# Filamint_Schematic.net
KiCad netlist of a schematic drawn in EAGLE
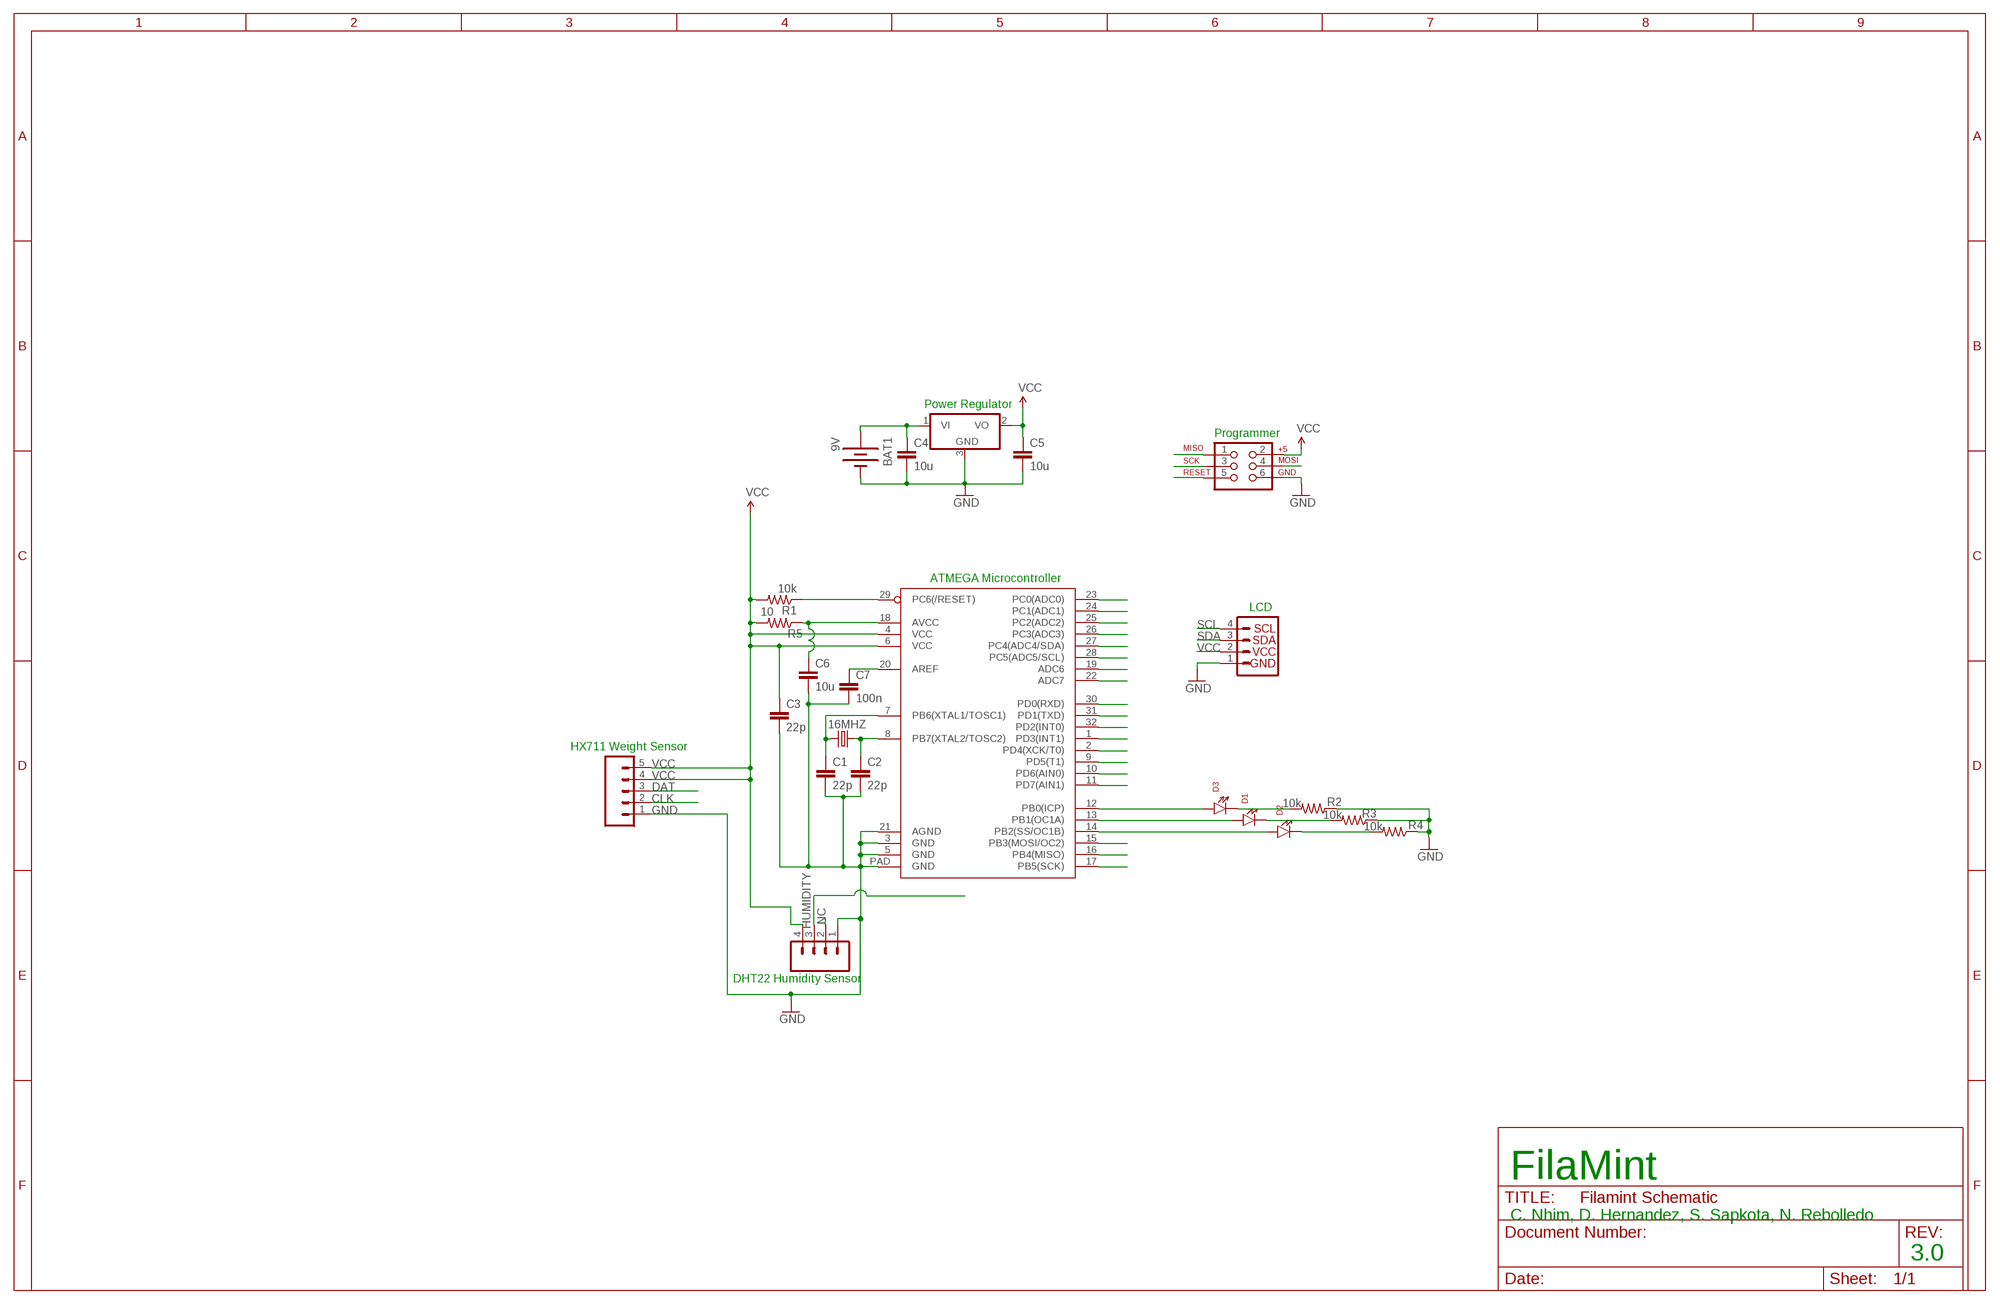
[diagram p0: schematic, sheet 1]

(export (version "E")
  (design (tool "Eeschema 10.0.6"))
  (components
    (comp (ref "16MHZ")
      (value "CSM-7X-DU")
      (footprint "eagle-import:CSM-7X-DU")
      (libsource (lib "eagle-import") (part "CSM-7X-DU"))
    )
    (comp (ref "BAT1")
      (value "9V")
      (footprint "eagle-import:BATTCON_9V")
      (libsource (lib "eagle-import") (part "BATTERY9V"))
    )
    (comp (ref "C1")
      (value "22p")
      (footprint "eagle-import:C025-024X044")
      (libsource (lib "eagle-import") (part "C-EU025-024X044"))
    )
    (comp (ref "C2")
      (value "22p")
      (footprint "eagle-import:C025-024X044")
      (libsource (lib "eagle-import") (part "C-EU025-024X044"))
    )
    (comp (ref "C3")
      (value "22p")
      (footprint "eagle-import:C025-024X044")
      (libsource (lib "eagle-import") (part "C-EU025-024X044"))
    )
    (comp (ref "C4")
      (value "10u")
      (footprint "eagle-import:C025-024X044")
      (libsource (lib "eagle-import") (part "C-EU025-024X044"))
    )
    (comp (ref "C5")
      (value "10u")
      (footprint "eagle-import:C025-024X044")
      (libsource (lib "eagle-import") (part "C-EU025-024X044"))
    )
    (comp (ref "C6")
      (value "10u")
      (footprint "eagle-import:C025-024X044")
      (libsource (lib "eagle-import") (part "C-EU025-024X044"))
    )
    (comp (ref "C7")
      (value "100n")
      (footprint "eagle-import:C025-024X044")
      (libsource (lib "eagle-import") (part "C-EU025-024X044"))
    )
    (comp (ref "D1")
      (value "LTE-302")
      (footprint "eagle-import:LTE-302")
      (libsource (lib "eagle-import") (part "LTE-302"))
    )
    (comp (ref "D2")
      (value "LTE-302")
      (footprint "eagle-import:LTE-302")
      (libsource (lib "eagle-import") (part "LTE-302"))
    )
    (comp (ref "D3")
      (value "LTE-302")
      (footprint "eagle-import:LTE-302")
      (libsource (lib "eagle-import") (part "LTE-302"))
    )
    (comp (ref "DHT22")
      (value "M04SMD2")
      (footprint "eagle-import:1X04-1MM-RA")
      (libsource (lib "eagle-import") (part "M04SMD2"))
    )
    (comp (ref "HX711")
      (value "M05SMD")
      (footprint "eagle-import:1X05-1MM")
      (libsource (lib "eagle-import") (part "M05SMD"))
    )
    (comp (ref "IC1")
      (value "7805DT")
      (footprint "eagle-import:TO252")
      (libsource (lib "eagle-import") (part "78DT05"))
    )
    (comp (ref "LCD")
      (value "I2C_STANDARD")
      (footprint "eagle-import:1X04")
      (libsource (lib "eagle-import") (part "I2C_STANDARD"))
    )
    (comp (ref "MICROCONTROLLER")
      (value "ATMEGA328P_MLFMLF32")
      (footprint "eagle-import:MLF32-PAD")
      (libsource (lib "eagle-import") (part "ATMEGA328P_MLFMLF32"))
    )
    (comp (ref "PROGRAMMER")
      (value "AVR_SPI_PRG_6PTH")
      (footprint "eagle-import:2X3")
      (libsource (lib "eagle-import") (part "AVR_SPI_PRG_6PTH"))
    )
    (comp (ref "R1")
      (value "10k")
      (footprint "eagle-import:0204_5")
      (libsource (lib "eagle-import") (part "R-US_0204/5"))
    )
    (comp (ref "R2")
      (value "10k")
      (footprint "eagle-import:0204_5")
      (libsource (lib "eagle-import") (part "R-US_0204/5"))
    )
    (comp (ref "R3")
      (value "10k")
      (footprint "eagle-import:0204_5")
      (libsource (lib "eagle-import") (part "R-US_0204/5"))
    )
    (comp (ref "R4")
      (value "10k")
      (footprint "eagle-import:0204_5")
      (libsource (lib "eagle-import") (part "R-US_0204/5"))
    )
    (comp (ref "R5")
      (value "10")
      (footprint "eagle-import:0204_5")
      (libsource (lib "eagle-import") (part "R-US_0204/5"))
    )
  )
  (nets
    (net (code "1") (name "/CLK") (class "Default")
      (node (ref "HX711") (pin "2") (pinfunction "2_2") (pintype "passive"))
    )
    (net (code "2") (name "/DAT") (class "Default")
      (node (ref "HX711") (pin "3") (pinfunction "3_3") (pintype "passive"))
    )
    (net (code "3") (name "/HUMIDITY") (class "Default")
      (node (ref "DHT22") (pin "3") (pinfunction "3_3") (pintype "passive"))
    )
    (net (code "4") (name "/MISO") (class "Default")
      (node (ref "MICROCONTROLLER") (pin "16") (pinfunction "PB4(MISO)_16") (pintype "bidirectional"))
      (node (ref "PROGRAMMER") (pin "1") (pinfunction "1_1") (pintype "passive"))
    )
    (net (code "5") (name "/MOSI") (class "Default")
      (node (ref "MICROCONTROLLER") (pin "15") (pinfunction "PB3(MOSI/OC2)_15") (pintype "bidirectional"))
      (node (ref "PROGRAMMER") (pin "4") (pinfunction "4_4") (pintype "passive"))
    )
    (net (code "6") (name "/NC") (class "Default")
      (node (ref "DHT22") (pin "2") (pinfunction "2_2") (pintype "passive"))
    )
    (net (code "7") (name "/SCK") (class "Default")
      (node (ref "MICROCONTROLLER") (pin "17") (pinfunction "PB5(SCK)_17") (pintype "bidirectional"))
      (node (ref "PROGRAMMER") (pin "3") (pinfunction "3_3") (pintype "passive"))
    )
    (net (code "8") (name "/SCL") (class "Default")
      (node (ref "LCD") (pin "4") (pinfunction "4_4") (pintype "passive"))
      (node (ref "MICROCONTROLLER") (pin "28") (pinfunction "PC5(ADC5/SCL)_28") (pintype "bidirectional"))
    )
    (net (code "9") (name "/SDA") (class "Default")
      (node (ref "LCD") (pin "3") (pinfunction "3_3") (pintype "passive"))
      (node (ref "MICROCONTROLLER") (pin "27") (pinfunction "PC4(ADC4/SDA)_27") (pintype "bidirectional"))
    )
    (net (code "10") (name "GND") (class "Default")
      (node (ref "BAT1") (pin "-") (pinfunction "-_-") (pintype "power_in"))
      (node (ref "C1") (pin "2") (pinfunction "2_2") (pintype "passive"))
      (node (ref "C2") (pin "2") (pinfunction "2_2") (pintype "passive"))
      (node (ref "C3") (pin "2") (pinfunction "2_2") (pintype "passive"))
      (node (ref "C4") (pin "2") (pinfunction "2_2") (pintype "passive"))
      (node (ref "C5") (pin "2") (pinfunction "2_2") (pintype "passive"))
      (node (ref "C6") (pin "2") (pinfunction "2_2") (pintype "passive"))
      (node (ref "C7") (pin "2") (pinfunction "2_2") (pintype "passive"))
      (node (ref "DHT22") (pin "1") (pinfunction "1_1") (pintype "passive"))
      (node (ref "HX711") (pin "1") (pinfunction "1_1") (pintype "passive"))
      (node (ref "IC1") (pin "3") (pinfunction "GND_3") (pintype "passive"))
      (node (ref "LCD") (pin "1") (pinfunction "1_1") (pintype "passive"))
      (node (ref "MICROCONTROLLER") (pin "21") (pinfunction "AGND_21") (pintype "bidirectional"))
      (node (ref "MICROCONTROLLER") (pin "3") (pinfunction "GND_3") (pintype "bidirectional"))
      (node (ref "MICROCONTROLLER") (pin "5") (pinfunction "GND_5") (pintype "bidirectional"))
      (node (ref "MICROCONTROLLER") (pin "PAD") (pinfunction "GND_PAD") (pintype "bidirectional"))
      (node (ref "PROGRAMMER") (pin "6") (pinfunction "6_6") (pintype "passive"))
      (node (ref "R2") (pin "1") (pinfunction "1_1") (pintype "passive"))
      (node (ref "R3") (pin "1") (pinfunction "1_1") (pintype "passive"))
      (node (ref "R4") (pin "1") (pinfunction "1_1") (pintype "passive"))
    )
    (net (code "11") (name "Net-(D1-PadC)") (class "Default")
      (node (ref "D1") (pin "C") (pinfunction "C_C") (pintype "bidirectional"))
      (node (ref "R3") (pin "2") (pinfunction "2_2") (pintype "passive"))
    )
    (net (code "12") (name "Net-(D2-PadC)") (class "Default")
      (node (ref "D2") (pin "C") (pinfunction "C_C") (pintype "bidirectional"))
      (node (ref "R4") (pin "2") (pinfunction "2_2") (pintype "passive"))
    )
    (net (code "13") (name "Net-(D3-PadC)") (class "Default")
      (node (ref "D3") (pin "C") (pinfunction "C_C") (pintype "bidirectional"))
      (node (ref "R2") (pin "2") (pinfunction "2_2") (pintype "passive"))
    )
    (net (code "14") (name "Net-(IC1-VI)") (class "Default")
      (node (ref "BAT1") (pin "+") (pinfunction "+_+") (pintype "power_in"))
      (node (ref "C4") (pin "1") (pinfunction "1_1") (pintype "passive"))
      (node (ref "IC1") (pin "1") (pinfunction "VI_1") (pintype "input"))
    )
    (net (code "15") (name "Net-(MICROCONTROLLER-AREF)") (class "Default")
      (node (ref "C7") (pin "1") (pinfunction "1_1") (pintype "passive"))
      (node (ref "MICROCONTROLLER") (pin "20") (pinfunction "AREF_20") (pintype "bidirectional"))
    )
    (net (code "16") (name "Net-(MICROCONTROLLER-AVCC)") (class "Default")
      (node (ref "C6") (pin "1") (pinfunction "1_1") (pintype "passive"))
      (node (ref "MICROCONTROLLER") (pin "18") (pinfunction "AVCC_18") (pintype "bidirectional"))
      (node (ref "R5") (pin "1") (pinfunction "1_1") (pintype "passive"))
    )
    (net (code "17") (name "Net-(MICROCONTROLLER-PB0(ICP))") (class "Default")
      (node (ref "D3") (pin "A") (pinfunction "A_A") (pintype "bidirectional"))
      (node (ref "MICROCONTROLLER") (pin "12") (pinfunction "PB0(ICP)_12") (pintype "bidirectional"))
    )
    (net (code "18") (name "Net-(MICROCONTROLLER-PB1(OC1A))") (class "Default")
      (node (ref "D1") (pin "A") (pinfunction "A_A") (pintype "bidirectional"))
      (node (ref "MICROCONTROLLER") (pin "13") (pinfunction "PB1(OC1A)_13") (pintype "bidirectional"))
    )
    (net (code "19") (name "Net-(MICROCONTROLLER-PB2(SS{slash}OC1B))") (class "Default")
      (node (ref "D2") (pin "A") (pinfunction "A_A") (pintype "bidirectional"))
      (node (ref "MICROCONTROLLER") (pin "14") (pinfunction "PB2(SS/OC1B)_14") (pintype "bidirectional"))
    )
    (net (code "20") (name "Net-(MICROCONTROLLER-PB6(XTAL1{slash}TOSC1))") (class "Default")
      (node (ref "16MHZ") (pin "2") (pinfunction "2_2") (pintype "passive"))
      (node (ref "C1") (pin "1") (pinfunction "1_1") (pintype "passive"))
      (node (ref "MICROCONTROLLER") (pin "7") (pinfunction "PB6(XTAL1/TOSC1)_7") (pintype "bidirectional"))
    )
    (net (code "21") (name "Net-(MICROCONTROLLER-PB7(XTAL2{slash}TOSC2))") (class "Default")
      (node (ref "16MHZ") (pin "1") (pinfunction "1_1") (pintype "passive"))
      (node (ref "C2") (pin "1") (pinfunction "1_1") (pintype "passive"))
      (node (ref "MICROCONTROLLER") (pin "8") (pinfunction "PB7(XTAL2/TOSC2)_8") (pintype "bidirectional"))
    )
    (net (code "22") (name "Net-(MICROCONTROLLER-PC6({slash}RESET))") (class "Default")
      (node (ref "MICROCONTROLLER") (pin "29") (pinfunction "PC6(/RESET)_29") (pintype "bidirectional"))
      (node (ref "R1") (pin "1") (pinfunction "1_1") (pintype "passive"))
    )
    (net (code "23") (name "VCC") (class "Default")
      (node (ref "C3") (pin "1") (pinfunction "1_1") (pintype "passive"))
      (node (ref "C5") (pin "1") (pinfunction "1_1") (pintype "passive"))
      (node (ref "DHT22") (pin "4") (pinfunction "4_4") (pintype "passive"))
      (node (ref "HX711") (pin "4") (pinfunction "4_4") (pintype "passive"))
      (node (ref "HX711") (pin "5") (pinfunction "5_5") (pintype "passive"))
      (node (ref "IC1") (pin "2") (pinfunction "VO_2") (pintype "passive"))
      (node (ref "LCD") (pin "2") (pinfunction "2_2") (pintype "passive"))
      (node (ref "MICROCONTROLLER") (pin "4") (pinfunction "VCC_4") (pintype "bidirectional"))
      (node (ref "MICROCONTROLLER") (pin "6") (pinfunction "VCC_6") (pintype "bidirectional"))
      (node (ref "PROGRAMMER") (pin "2") (pinfunction "2_2") (pintype "passive"))
      (node (ref "R1") (pin "2") (pinfunction "2_2") (pintype "passive"))
      (node (ref "R5") (pin "2") (pinfunction "2_2") (pintype "passive"))
    )
    (net (code "24") (name "unconnected-(MICROCONTROLLER-ADC6-Pad19)") (class "Default")
      (node (ref "MICROCONTROLLER") (pin "19") (pinfunction "ADC6_19") (pintype "bidirectional"))
    )
    (net (code "25") (name "unconnected-(MICROCONTROLLER-ADC7-Pad22)") (class "Default")
      (node (ref "MICROCONTROLLER") (pin "22") (pinfunction "ADC7_22") (pintype "bidirectional"))
    )
    (net (code "26") (name "unconnected-(MICROCONTROLLER-PC0(ADC0)-Pad23)") (class "Default")
      (node (ref "MICROCONTROLLER") (pin "23") (pinfunction "PC0(ADC0)_23") (pintype "bidirectional"))
    )
    (net (code "27") (name "unconnected-(MICROCONTROLLER-PC1(ADC1)-Pad24)") (class "Default")
      (node (ref "MICROCONTROLLER") (pin "24") (pinfunction "PC1(ADC1)_24") (pintype "bidirectional"))
    )
    (net (code "28") (name "unconnected-(MICROCONTROLLER-PC2(ADC2)-Pad25)") (class "Default")
      (node (ref "MICROCONTROLLER") (pin "25") (pinfunction "PC2(ADC2)_25") (pintype "bidirectional"))
    )
    (net (code "29") (name "unconnected-(MICROCONTROLLER-PC3(ADC3)-Pad26)") (class "Default")
      (node (ref "MICROCONTROLLER") (pin "26") (pinfunction "PC3(ADC3)_26") (pintype "bidirectional"))
    )
    (net (code "30") (name "unconnected-(MICROCONTROLLER-PD0(RXD)-Pad30)") (class "Default")
      (node (ref "MICROCONTROLLER") (pin "30") (pinfunction "PD0(RXD)_30") (pintype "bidirectional"))
    )
    (net (code "31") (name "unconnected-(MICROCONTROLLER-PD1(TXD)-Pad31)") (class "Default")
      (node (ref "MICROCONTROLLER") (pin "31") (pinfunction "PD1(TXD)_31") (pintype "bidirectional"))
    )
    (net (code "32") (name "unconnected-(MICROCONTROLLER-PD2(INT0)-Pad32)") (class "Default")
      (node (ref "MICROCONTROLLER") (pin "32") (pinfunction "PD2(INT0)_32") (pintype "bidirectional"))
    )
    (net (code "33") (name "unconnected-(MICROCONTROLLER-PD3(INT1)-Pad1)") (class "Default")
      (node (ref "MICROCONTROLLER") (pin "1") (pinfunction "PD3(INT1)_1") (pintype "bidirectional"))
    )
    (net (code "34") (name "unconnected-(MICROCONTROLLER-PD4(XCK{slash}T0)-Pad2)") (class "Default")
      (node (ref "MICROCONTROLLER") (pin "2") (pinfunction "PD4(XCK/T0)_2") (pintype "bidirectional"))
    )
    (net (code "35") (name "unconnected-(MICROCONTROLLER-PD5(T1)-Pad9)") (class "Default")
      (node (ref "MICROCONTROLLER") (pin "9") (pinfunction "PD5(T1)_9") (pintype "bidirectional"))
    )
    (net (code "36") (name "unconnected-(MICROCONTROLLER-PD6(AIN0)-Pad10)") (class "Default")
      (node (ref "MICROCONTROLLER") (pin "10") (pinfunction "PD6(AIN0)_10") (pintype "bidirectional"))
    )
    (net (code "37") (name "unconnected-(MICROCONTROLLER-PD7(AIN1)-Pad11)") (class "Default")
      (node (ref "MICROCONTROLLER") (pin "11") (pinfunction "PD7(AIN1)_11") (pintype "bidirectional"))
    )
    (net (code "38") (name "unconnected-(PROGRAMMER-Pad5)") (class "Default")
      (node (ref "PROGRAMMER") (pin "5") (pinfunction "5_5") (pintype "passive"))
    )
  )
)
